# ESPGith.net
KiCad netlist of a schematic drawn in Altium Designer
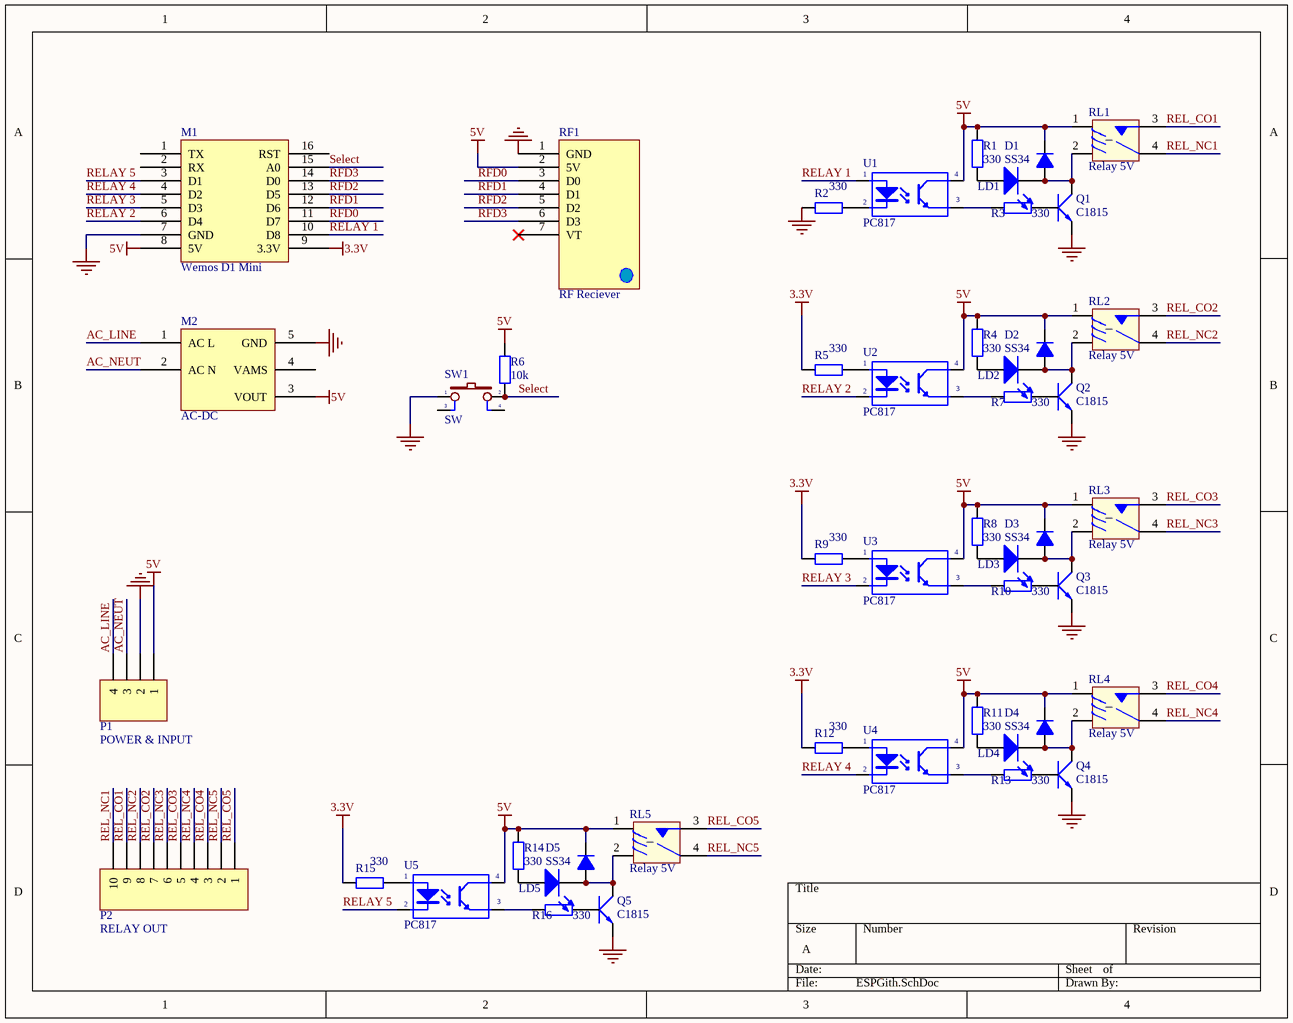
[diagram p0: ESPGith.SchDoc]

(export (version "E")
  (design (tool "Eeschema 10.0.6"))
  (components
    (comp (ref "D1")
      (value "SS34")
      (footprint "DO-214AC")
      (description "Diode 1A")
      (libsource (lib "VioletofSun") (part "D1A"))
    )
    (comp (ref "D2")
      (value "SS34")
      (footprint "DO-214AC")
      (description "Diode 1A")
      (libsource (lib "VioletofSun") (part "D1A"))
    )
    (comp (ref "D3")
      (value "SS34")
      (footprint "DO-214AC")
      (description "Diode 1A")
      (libsource (lib "VioletofSun") (part "D1A"))
    )
    (comp (ref "D4")
      (value "SS34")
      (footprint "DO-214AC")
      (description "Diode 1A")
      (libsource (lib "VioletofSun") (part "D1A"))
    )
    (comp (ref "D5")
      (value "SS34")
      (footprint "DO-214AC")
      (description "Diode 1A")
      (libsource (lib "VioletofSun") (part "D1A"))
    )
    (comp (ref "LD1")
      (value "CONNECTION")
      (footprint "LED-3mm Yellow")
      (description "Typical RED, GREEN, YELLOW, AMBER GaAs LED")
      (fields (field (name "PUBLISHER") "Altium Limited"))
      (libsource (lib "Miscellaneous Devices") (part "LED2"))
    )
    (comp (ref "LD2")
      (value "CONNECTION")
      (footprint "LED-3mm Yellow")
      (description "Typical RED, GREEN, YELLOW, AMBER GaAs LED")
      (fields (field (name "PUBLISHER") "Altium Limited"))
      (libsource (lib "Miscellaneous Devices") (part "LED2"))
    )
    (comp (ref "LD3")
      (value "CONNECTION")
      (footprint "LED-3mm Yellow")
      (description "Typical RED, GREEN, YELLOW, AMBER GaAs LED")
      (fields (field (name "PUBLISHER") "Altium Limited"))
      (libsource (lib "Miscellaneous Devices") (part "LED2"))
    )
    (comp (ref "LD4")
      (value "CONNECTION")
      (footprint "LED-3mm Yellow")
      (description "Typical RED, GREEN, YELLOW, AMBER GaAs LED")
      (fields (field (name "PUBLISHER") "Altium Limited"))
      (libsource (lib "Miscellaneous Devices") (part "LED2"))
    )
    (comp (ref "LD5")
      (value "CONNECTION")
      (footprint "LED-3mm Yellow")
      (description "Typical RED, GREEN, YELLOW, AMBER GaAs LED")
      (fields (field (name "PUBLISHER") "Altium Limited"))
      (libsource (lib "Miscellaneous Devices") (part "LED2"))
    )
    (comp (ref "M1")
      (value "Wemos D1 Mini")
      (footprint "Wemos D1 Mini")
      (libsource (lib "DuyLuan") (part "Wemos D1 Mini"))
    )
    (comp (ref "M2")
      (value "AC-DC")
      (footprint "AC-DC 5V3W")
      (description "AC -> DC 5V 3W")
      (libsource (lib "DuyLuan") (part "AC-DC 5V3W"))
    )
    (comp (ref "P1")
      (value "POWER & INPUT")
      (footprint "TB 4 RA 3.81")
      (description "Header, 4-Pin")
      (fields (field (name "PUBLISHER") "Altium Limited"))
      (libsource (lib "NBBLib 14-03-2012") (part "Header 4"))
    )
    (comp (ref "P2")
      (value "RELAY OUT")
      (footprint "TB 10 RA 3.81")
      (description "Header, 10-Pin")
      (fields (field (name "PUBLISHER") "Altium Limited"))
      (libsource (lib "NBBLib 14-03-2012") (part "Header 10"))
    )
    (comp (ref "Q1")
      (value "C1815")
      (footprint "SOT23-3")
      (description "NPN 600mW, ECB")
      (libsource (lib "VioletofSun") (part "C1815"))
    )
    (comp (ref "Q2")
      (value "C1815")
      (footprint "SOT23-3")
      (description "NPN 600mW, ECB")
      (libsource (lib "VioletofSun") (part "C1815"))
    )
    (comp (ref "Q3")
      (value "C1815")
      (footprint "SOT23-3")
      (description "NPN 600mW, ECB")
      (libsource (lib "VioletofSun") (part "C1815"))
    )
    (comp (ref "Q4")
      (value "C1815")
      (footprint "SOT23-3")
      (description "NPN 600mW, ECB")
      (libsource (lib "VioletofSun") (part "C1815"))
    )
    (comp (ref "Q5")
      (value "C1815")
      (footprint "SOT23-3")
      (description "NPN 600mW, ECB")
      (libsource (lib "VioletofSun") (part "C1815"))
    )
    (comp (ref "R1")
      (value "330")
      (footprint "RESC2012N_F")
      (description "Resistor")
      (fields (field (name "Comment") "220") (field (name "PUBLISHER") "Altium Limited"))
      (libsource (lib "NBBLib 14-03-2012") (part "Res 1/4 W"))
    )
    (comp (ref "R2")
      (value "330")
      (footprint "RESC2012N_F")
      (description "Resistor 1/4W")
      (libsource (lib "VioletofSun") (part "R1/4W"))
    )
    (comp (ref "R3")
      (value "330")
      (footprint "RESC2012N_F")
      (description "Resistor 1/4W")
      (libsource (lib "VioletofSun") (part "R1/4W"))
    )
    (comp (ref "R4")
      (value "330")
      (footprint "RESC2012N_F")
      (description "Resistor")
      (fields (field (name "Comment") "220") (field (name "PUBLISHER") "Altium Limited"))
      (libsource (lib "NBBLib 14-03-2012") (part "Res 1/4 W"))
    )
    (comp (ref "R5")
      (value "330")
      (footprint "RESC2012N_F")
      (description "Resistor 1/4W")
      (libsource (lib "VioletofSun") (part "R1/4W"))
    )
    (comp (ref "R6")
      (value "10k")
      (footprint "RESC2012N_F")
      (description "Resistor SMD 0805")
      (fields (field (name "PUBLISHER") "Altium Limited"))
      (libsource (lib "NBBLib 14-03-2012") (part "R0805"))
    )
    (comp (ref "R7")
      (value "330")
      (footprint "RESC2012N_F")
      (description "Resistor 1/4W")
      (libsource (lib "VioletofSun") (part "R1/4W"))
    )
    (comp (ref "R8")
      (value "330")
      (footprint "RESC2012N_F")
      (description "Resistor")
      (fields (field (name "Comment") "220") (field (name "PUBLISHER") "Altium Limited"))
      (libsource (lib "NBBLib 14-03-2012") (part "Res 1/4 W"))
    )
    (comp (ref "R9")
      (value "330")
      (footprint "RESC2012N_F")
      (description "Resistor 1/4W")
      (libsource (lib "VioletofSun") (part "R1/4W"))
    )
    (comp (ref "R10")
      (value "330")
      (footprint "RESC2012N_F")
      (description "Resistor 1/4W")
      (libsource (lib "VioletofSun") (part "R1/4W"))
    )
    (comp (ref "R11")
      (value "330")
      (footprint "RESC2012N_F")
      (description "Resistor")
      (fields (field (name "Comment") "220") (field (name "PUBLISHER") "Altium Limited"))
      (libsource (lib "NBBLib 14-03-2012") (part "Res 1/4 W"))
    )
    (comp (ref "R12")
      (value "330")
      (footprint "RESC2012N_F")
      (description "Resistor 1/4W")
      (libsource (lib "VioletofSun") (part "R1/4W"))
    )
    (comp (ref "R13")
      (value "330")
      (footprint "RESC2012N_F")
      (description "Resistor 1/4W")
      (libsource (lib "VioletofSun") (part "R1/4W"))
    )
    (comp (ref "R14")
      (value "330")
      (footprint "RESC2012N_F")
      (description "Resistor")
      (fields (field (name "Comment") "220") (field (name "PUBLISHER") "Altium Limited"))
      (libsource (lib "NBBLib 14-03-2012") (part "Res 1/4 W"))
    )
    (comp (ref "R15")
      (value "330")
      (footprint "RESC2012N_F")
      (description "Resistor 1/4W")
      (libsource (lib "VioletofSun") (part "R1/4W"))
    )
    (comp (ref "R16")
      (value "330")
      (footprint "RESC2012N_F")
      (description "Resistor 1/4W")
      (libsource (lib "VioletofSun") (part "R1/4W"))
    )
    (comp (ref "RF1")
      (value "RF Reciever")
      (footprint "RF Reciever")
      (libsource (lib "DuyLuan") (part "RF Reciever"))
    )
    (comp (ref "RL1")
      (value "Relay 5V")
      (footprint "DuyLuan:RL_HF46F")
      (description "Relay SPDT,10A - 12VDC 5 Pin")
      (libsource (lib "DuyLuan") (part "Relay 3"))
    )
    (comp (ref "RL2")
      (value "Relay 5V")
      (footprint "DuyLuan:RL_HF46F")
      (description "Relay SPDT,10A - 12VDC 5 Pin")
      (libsource (lib "DuyLuan") (part "Relay 3"))
    )
    (comp (ref "RL3")
      (value "Relay 5V")
      (footprint "DuyLuan:RL_HF46F")
      (description "Relay SPDT,10A - 12VDC 5 Pin")
      (libsource (lib "DuyLuan") (part "Relay 3"))
    )
    (comp (ref "RL4")
      (value "Relay 5V")
      (footprint "DuyLuan:RL_HF46F")
      (description "Relay SPDT,10A - 12VDC 5 Pin")
      (libsource (lib "DuyLuan") (part "Relay 3"))
    )
    (comp (ref "RL5")
      (value "Relay 5V")
      (footprint "DuyLuan:RL_HF46F")
      (description "Relay SPDT,10A - 12VDC 5 Pin")
      (libsource (lib "DuyLuan") (part "Relay 3"))
    )
    (comp (ref "SW1")
      (value "SW")
      (footprint "SW4")
      (description "Switch button 4 pin")
      (libsource (lib "DuyLuan") (part "SW4-1"))
    )
    (comp (ref "U1")
      (value "PC817")
      (footprint "DIP4/W0.3")
      (description "Single Opto")
      (libsource (lib "DuyLuan") (part "PC817"))
    )
    (comp (ref "U2")
      (value "PC817")
      (footprint "DIP4/W0.3")
      (description "Single Opto")
      (libsource (lib "DuyLuan") (part "PC817"))
    )
    (comp (ref "U3")
      (value "PC817")
      (footprint "DIP4/W0.3")
      (description "Single Opto")
      (libsource (lib "DuyLuan") (part "PC817"))
    )
    (comp (ref "U4")
      (value "PC817")
      (footprint "DIP4/W0.3")
      (description "Single Opto")
      (libsource (lib "DuyLuan") (part "PC817"))
    )
    (comp (ref "U5")
      (value "PC817")
      (footprint "DIP4/W0.3")
      (description "Single Opto")
      (libsource (lib "DuyLuan") (part "PC817"))
    )
  )
  (nets
    (net (code "1") (name "/AC_LINE") (class "Default")
      (node (ref "M2") (pin "1") (pinfunction "AC_L_1") (pintype "passive"))
      (node (ref "P1") (pin "4") (pinfunction "4_4") (pintype "passive"))
    )
    (net (code "2") (name "/AC_NEUT") (class "Default")
      (node (ref "M2") (pin "2") (pinfunction "AC_N_2") (pintype "passive"))
      (node (ref "P1") (pin "3") (pinfunction "3_3") (pintype "passive"))
    )
    (net (code "3") (name "/RELAY 1") (class "Default")
      (node (ref "M1") (pin "10") (pinfunction "D8_10") (pintype "passive"))
      (node (ref "U1") (pin "1") (pinfunction "A_1") (pintype "passive"))
    )
    (net (code "4") (name "/RELAY 2") (class "Default")
      (node (ref "M1") (pin "6") (pinfunction "D4_6") (pintype "passive"))
      (node (ref "U2") (pin "2") (pinfunction "K_2") (pintype "passive"))
    )
    (net (code "5") (name "/RELAY 3") (class "Default")
      (node (ref "M1") (pin "5") (pinfunction "D3_5") (pintype "passive"))
      (node (ref "U3") (pin "2") (pinfunction "K_2") (pintype "passive"))
    )
    (net (code "6") (name "/RELAY 4") (class "Default")
      (node (ref "M1") (pin "4") (pinfunction "D2_4") (pintype "passive"))
      (node (ref "U4") (pin "2") (pinfunction "K_2") (pintype "passive"))
    )
    (net (code "7") (name "/RELAY 5") (class "Default")
      (node (ref "M1") (pin "3") (pinfunction "D1_3") (pintype "passive"))
      (node (ref "U5") (pin "2") (pinfunction "K_2") (pintype "passive"))
    )
    (net (code "8") (name "/REL_CO1") (class "Default")
      (node (ref "P2") (pin "9") (pinfunction "9_9") (pintype "passive"))
      (node (ref "RL1") (pin "3") (pinfunction "3_3") (pintype "passive"))
    )
    (net (code "9") (name "/REL_CO2") (class "Default")
      (node (ref "P2") (pin "7") (pinfunction "7_7") (pintype "passive"))
      (node (ref "RL2") (pin "3") (pinfunction "3_3") (pintype "passive"))
    )
    (net (code "10") (name "/REL_CO3") (class "Default")
      (node (ref "P2") (pin "5") (pinfunction "5_5") (pintype "passive"))
      (node (ref "RL3") (pin "3") (pinfunction "3_3") (pintype "passive"))
    )
    (net (code "11") (name "/REL_CO4") (class "Default")
      (node (ref "P2") (pin "3") (pinfunction "3_3") (pintype "passive"))
      (node (ref "RL4") (pin "3") (pinfunction "3_3") (pintype "passive"))
    )
    (net (code "12") (name "/REL_CO5") (class "Default")
      (node (ref "P2") (pin "1") (pinfunction "1_1") (pintype "passive"))
      (node (ref "RL5") (pin "3") (pinfunction "3_3") (pintype "passive"))
    )
    (net (code "13") (name "/REL_NC1") (class "Default")
      (node (ref "P2") (pin "10") (pinfunction "10_10") (pintype "passive"))
      (node (ref "RL1") (pin "4") (pinfunction "4_4") (pintype "passive"))
    )
    (net (code "14") (name "/REL_NC2") (class "Default")
      (node (ref "P2") (pin "8") (pinfunction "8_8") (pintype "passive"))
      (node (ref "RL2") (pin "4") (pinfunction "4_4") (pintype "passive"))
    )
    (net (code "15") (name "/REL_NC3") (class "Default")
      (node (ref "P2") (pin "6") (pinfunction "6_6") (pintype "passive"))
      (node (ref "RL3") (pin "4") (pinfunction "4_4") (pintype "passive"))
    )
    (net (code "16") (name "/REL_NC4") (class "Default")
      (node (ref "P2") (pin "4") (pinfunction "4_4") (pintype "passive"))
      (node (ref "RL4") (pin "4") (pinfunction "4_4") (pintype "passive"))
    )
    (net (code "17") (name "/REL_NC5") (class "Default")
      (node (ref "P2") (pin "2") (pinfunction "2_2") (pintype "passive"))
      (node (ref "RL5") (pin "4") (pinfunction "4_4") (pintype "passive"))
    )
    (net (code "18") (name "/RFD0") (class "Default")
      (node (ref "M1") (pin "11") (pinfunction "D7_11") (pintype "passive"))
      (node (ref "RF1") (pin "3") (pinfunction "D0_3") (pintype "passive"))
    )
    (net (code "19") (name "/RFD1") (class "Default")
      (node (ref "M1") (pin "12") (pinfunction "D6_12") (pintype "passive"))
      (node (ref "RF1") (pin "4") (pinfunction "D1_4") (pintype "passive"))
    )
    (net (code "20") (name "/RFD2") (class "Default")
      (node (ref "M1") (pin "13") (pinfunction "D5_13") (pintype "passive"))
      (node (ref "RF1") (pin "5") (pinfunction "D2_5") (pintype "passive"))
    )
    (net (code "21") (name "/RFD3") (class "Default")
      (node (ref "M1") (pin "14") (pinfunction "D0_14") (pintype "passive"))
      (node (ref "RF1") (pin "6") (pinfunction "D3_6") (pintype "passive"))
    )
    (net (code "22") (name "/Select") (class "Default")
      (node (ref "M1") (pin "15") (pinfunction "A0_15") (pintype "passive"))
      (node (ref "R6") (pin "1") (pinfunction "1_1") (pintype "passive"))
      (node (ref "SW1") (pin "2") (pinfunction "2_2") (pintype "passive"))
    )
    (net (code "23") (name "3.3V") (class "Default")
      (node (ref "M1") (pin "9") (pinfunction "3.3V_9") (pintype "passive"))
      (node (ref "R12") (pin "2") (pinfunction "2_2") (pintype "passive"))
      (node (ref "R15") (pin "2") (pinfunction "2_2") (pintype "passive"))
      (node (ref "R5") (pin "2") (pinfunction "2_2") (pintype "passive"))
      (node (ref "R9") (pin "2") (pinfunction "2_2") (pintype "passive"))
    )
    (net (code "24") (name "5V") (class "Default")
      (node (ref "D1") (pin "K") (pinfunction "K_K") (pintype "passive"))
      (node (ref "D2") (pin "K") (pinfunction "K_K") (pintype "passive"))
      (node (ref "D3") (pin "K") (pinfunction "K_K") (pintype "passive"))
      (node (ref "D4") (pin "K") (pinfunction "K_K") (pintype "passive"))
      (node (ref "D5") (pin "K") (pinfunction "K_K") (pintype "passive"))
      (node (ref "M1") (pin "8") (pinfunction "5V_8") (pintype "passive"))
      (node (ref "M2") (pin "3") (pinfunction "VOUT_3") (pintype "passive"))
      (node (ref "P1") (pin "1") (pinfunction "1_1") (pintype "passive"))
      (node (ref "R1") (pin "2") (pinfunction "2_2") (pintype "passive"))
      (node (ref "R11") (pin "2") (pinfunction "2_2") (pintype "passive"))
      (node (ref "R14") (pin "2") (pinfunction "2_2") (pintype "passive"))
      (node (ref "R4") (pin "2") (pinfunction "2_2") (pintype "passive"))
      (node (ref "R6") (pin "2") (pinfunction "2_2") (pintype "passive"))
      (node (ref "R8") (pin "2") (pinfunction "2_2") (pintype "passive"))
      (node (ref "RF1") (pin "2") (pinfunction "5V_2") (pintype "passive"))
      (node (ref "RL1") (pin "1") (pinfunction "1_1") (pintype "passive"))
      (node (ref "RL2") (pin "1") (pinfunction "1_1") (pintype "passive"))
      (node (ref "RL3") (pin "1") (pinfunction "1_1") (pintype "passive"))
      (node (ref "RL4") (pin "1") (pinfunction "1_1") (pintype "passive"))
      (node (ref "RL5") (pin "1") (pinfunction "1_1") (pintype "passive"))
      (node (ref "U1") (pin "4") (pinfunction "C_4") (pintype "passive"))
      (node (ref "U2") (pin "4") (pinfunction "C_4") (pintype "passive"))
      (node (ref "U3") (pin "4") (pinfunction "C_4") (pintype "passive"))
      (node (ref "U4") (pin "4") (pinfunction "C_4") (pintype "passive"))
      (node (ref "U5") (pin "4") (pinfunction "C_4") (pintype "passive"))
    )
    (net (code "25") (name "GND") (class "Default")
      (node (ref "M1") (pin "7") (pinfunction "GND_7") (pintype "passive"))
      (node (ref "M2") (pin "5") (pinfunction "GND_5") (pintype "passive"))
      (node (ref "P1") (pin "2") (pinfunction "2_2") (pintype "passive"))
      (node (ref "Q1") (pin "2") (pinfunction "E_2") (pintype "passive"))
      (node (ref "Q2") (pin "2") (pinfunction "E_2") (pintype "passive"))
      (node (ref "Q3") (pin "2") (pinfunction "E_2") (pintype "passive"))
      (node (ref "Q4") (pin "2") (pinfunction "E_2") (pintype "passive"))
      (node (ref "Q5") (pin "2") (pinfunction "E_2") (pintype "passive"))
      (node (ref "R2") (pin "2") (pinfunction "2_2") (pintype "passive"))
      (node (ref "RF1") (pin "1") (pinfunction "GND_1") (pintype "passive"))
      (node (ref "SW1") (pin "1") (pinfunction "1_1") (pintype "passive"))
    )
    (net (code "26") (name "Net-(LD1-A)") (class "Default")
      (node (ref "LD1") (pin "1") (pinfunction "A_1") (pintype "passive"))
      (node (ref "R1") (pin "1") (pinfunction "1_1") (pintype "passive"))
    )
    (net (code "27") (name "Net-(LD1-K)") (class "Default")
      (node (ref "D1") (pin "A") (pinfunction "A_A") (pintype "passive"))
      (node (ref "LD1") (pin "2") (pinfunction "K_2") (pintype "passive"))
      (node (ref "Q1") (pin "3") (pinfunction "C_3") (pintype "passive"))
      (node (ref "RL1") (pin "2") (pinfunction "2_2") (pintype "passive"))
    )
    (net (code "28") (name "Net-(LD2-A)") (class "Default")
      (node (ref "LD2") (pin "1") (pinfunction "A_1") (pintype "passive"))
      (node (ref "R4") (pin "1") (pinfunction "1_1") (pintype "passive"))
    )
    (net (code "29") (name "Net-(LD2-K)") (class "Default")
      (node (ref "D2") (pin "A") (pinfunction "A_A") (pintype "passive"))
      (node (ref "LD2") (pin "2") (pinfunction "K_2") (pintype "passive"))
      (node (ref "Q2") (pin "3") (pinfunction "C_3") (pintype "passive"))
      (node (ref "RL2") (pin "2") (pinfunction "2_2") (pintype "passive"))
    )
    (net (code "30") (name "Net-(LD3-A)") (class "Default")
      (node (ref "LD3") (pin "1") (pinfunction "A_1") (pintype "passive"))
      (node (ref "R8") (pin "1") (pinfunction "1_1") (pintype "passive"))
    )
    (net (code "31") (name "Net-(LD3-K)") (class "Default")
      (node (ref "D3") (pin "A") (pinfunction "A_A") (pintype "passive"))
      (node (ref "LD3") (pin "2") (pinfunction "K_2") (pintype "passive"))
      (node (ref "Q3") (pin "3") (pinfunction "C_3") (pintype "passive"))
      (node (ref "RL3") (pin "2") (pinfunction "2_2") (pintype "passive"))
    )
    (net (code "32") (name "Net-(LD4-A)") (class "Default")
      (node (ref "LD4") (pin "1") (pinfunction "A_1") (pintype "passive"))
      (node (ref "R11") (pin "1") (pinfunction "1_1") (pintype "passive"))
    )
    (net (code "33") (name "Net-(LD4-K)") (class "Default")
      (node (ref "D4") (pin "A") (pinfunction "A_A") (pintype "passive"))
      (node (ref "LD4") (pin "2") (pinfunction "K_2") (pintype "passive"))
      (node (ref "Q4") (pin "3") (pinfunction "C_3") (pintype "passive"))
      (node (ref "RL4") (pin "2") (pinfunction "2_2") (pintype "passive"))
    )
    (net (code "34") (name "Net-(LD5-A)") (class "Default")
      (node (ref "LD5") (pin "1") (pinfunction "A_1") (pintype "passive"))
      (node (ref "R14") (pin "1") (pinfunction "1_1") (pintype "passive"))
    )
    (net (code "35") (name "Net-(LD5-K)") (class "Default")
      (node (ref "D5") (pin "A") (pinfunction "A_A") (pintype "passive"))
      (node (ref "LD5") (pin "2") (pinfunction "K_2") (pintype "passive"))
      (node (ref "Q5") (pin "3") (pinfunction "C_3") (pintype "passive"))
      (node (ref "RL5") (pin "2") (pinfunction "2_2") (pintype "passive"))
    )
    (net (code "36") (name "Net-(Q1-B)") (class "Default")
      (node (ref "Q1") (pin "1") (pinfunction "B_1") (pintype "passive"))
      (node (ref "R3") (pin "2") (pinfunction "2_2") (pintype "passive"))
    )
    (net (code "37") (name "Net-(Q2-B)") (class "Default")
      (node (ref "Q2") (pin "1") (pinfunction "B_1") (pintype "passive"))
      (node (ref "R7") (pin "2") (pinfunction "2_2") (pintype "passive"))
    )
    (net (code "38") (name "Net-(Q3-B)") (class "Default")
      (node (ref "Q3") (pin "1") (pinfunction "B_1") (pintype "passive"))
      (node (ref "R10") (pin "2") (pinfunction "2_2") (pintype "passive"))
    )
    (net (code "39") (name "Net-(Q4-B)") (class "Default")
      (node (ref "Q4") (pin "1") (pinfunction "B_1") (pintype "passive"))
      (node (ref "R13") (pin "2") (pinfunction "2_2") (pintype "passive"))
    )
    (net (code "40") (name "Net-(Q5-B)") (class "Default")
      (node (ref "Q5") (pin "1") (pinfunction "B_1") (pintype "passive"))
      (node (ref "R16") (pin "2") (pinfunction "2_2") (pintype "passive"))
    )
    (net (code "41") (name "Net-(U1-E)") (class "Default")
      (node (ref "R3") (pin "1") (pinfunction "1_1") (pintype "passive"))
      (node (ref "U1") (pin "3") (pinfunction "E_3") (pintype "passive"))
    )
    (net (code "42") (name "Net-(U1-K)") (class "Default")
      (node (ref "R2") (pin "1") (pinfunction "1_1") (pintype "passive"))
      (node (ref "U1") (pin "2") (pinfunction "K_2") (pintype "passive"))
    )
    (net (code "43") (name "Net-(U2-A)") (class "Default")
      (node (ref "R5") (pin "1") (pinfunction "1_1") (pintype "passive"))
      (node (ref "U2") (pin "1") (pinfunction "A_1") (pintype "passive"))
    )
    (net (code "44") (name "Net-(U2-E)") (class "Default")
      (node (ref "R7") (pin "1") (pinfunction "1_1") (pintype "passive"))
      (node (ref "U2") (pin "3") (pinfunction "E_3") (pintype "passive"))
    )
    (net (code "45") (name "Net-(U3-A)") (class "Default")
      (node (ref "R9") (pin "1") (pinfunction "1_1") (pintype "passive"))
      (node (ref "U3") (pin "1") (pinfunction "A_1") (pintype "passive"))
    )
    (net (code "46") (name "Net-(U3-E)") (class "Default")
      (node (ref "R10") (pin "1") (pinfunction "1_1") (pintype "passive"))
      (node (ref "U3") (pin "3") (pinfunction "E_3") (pintype "passive"))
    )
    (net (code "47") (name "Net-(U4-A)") (class "Default")
      (node (ref "R12") (pin "1") (pinfunction "1_1") (pintype "passive"))
      (node (ref "U4") (pin "1") (pinfunction "A_1") (pintype "passive"))
    )
    (net (code "48") (name "Net-(U4-E)") (class "Default")
      (node (ref "R13") (pin "1") (pinfunction "1_1") (pintype "passive"))
      (node (ref "U4") (pin "3") (pinfunction "E_3") (pintype "passive"))
    )
    (net (code "49") (name "Net-(U5-A)") (class "Default")
      (node (ref "R15") (pin "1") (pinfunction "1_1") (pintype "passive"))
      (node (ref "U5") (pin "1") (pinfunction "A_1") (pintype "passive"))
    )
    (net (code "50") (name "Net-(U5-E)") (class "Default")
      (node (ref "R16") (pin "1") (pinfunction "1_1") (pintype "passive"))
      (node (ref "U5") (pin "3") (pinfunction "E_3") (pintype "passive"))
    )
    (net (code "51") (name "unconnected-(M1-RST-Pad16)") (class "Default")
      (node (ref "M1") (pin "16") (pinfunction "RST_16") (pintype "passive"))
    )
    (net (code "52") (name "unconnected-(M1-RX-Pad2)") (class "Default")
      (node (ref "M1") (pin "2") (pinfunction "RX_2") (pintype "passive"))
    )
    (net (code "53") (name "unconnected-(M1-TX-Pad1)") (class "Default")
      (node (ref "M1") (pin "1") (pinfunction "TX_1") (pintype "passive"))
    )
    (net (code "54") (name "unconnected-(M2-VAMS-Pad4)") (class "Default")
      (node (ref "M2") (pin "4") (pinfunction "VAMS_4") (pintype "passive"))
    )
    (net (code "55") (name "unconnected-(RF1-VT-Pad7)") (class "Default")
      (node (ref "RF1") (pin "7") (pinfunction "VT_7") (pintype "passive+no_connect"))
    )
    (net (code "56") (name "unconnected-(SW1-Pad3)") (class "Default")
      (node (ref "SW1") (pin "3") (pinfunction "3_3") (pintype "passive"))
    )
    (net (code "57") (name "unconnected-(SW1-Pad4)") (class "Default")
      (node (ref "SW1") (pin "4") (pinfunction "4_4") (pintype "passive"))
    )
  )
)
